# AMS_MCU.net
KiCad netlist of a schematic drawn in Altium Designer
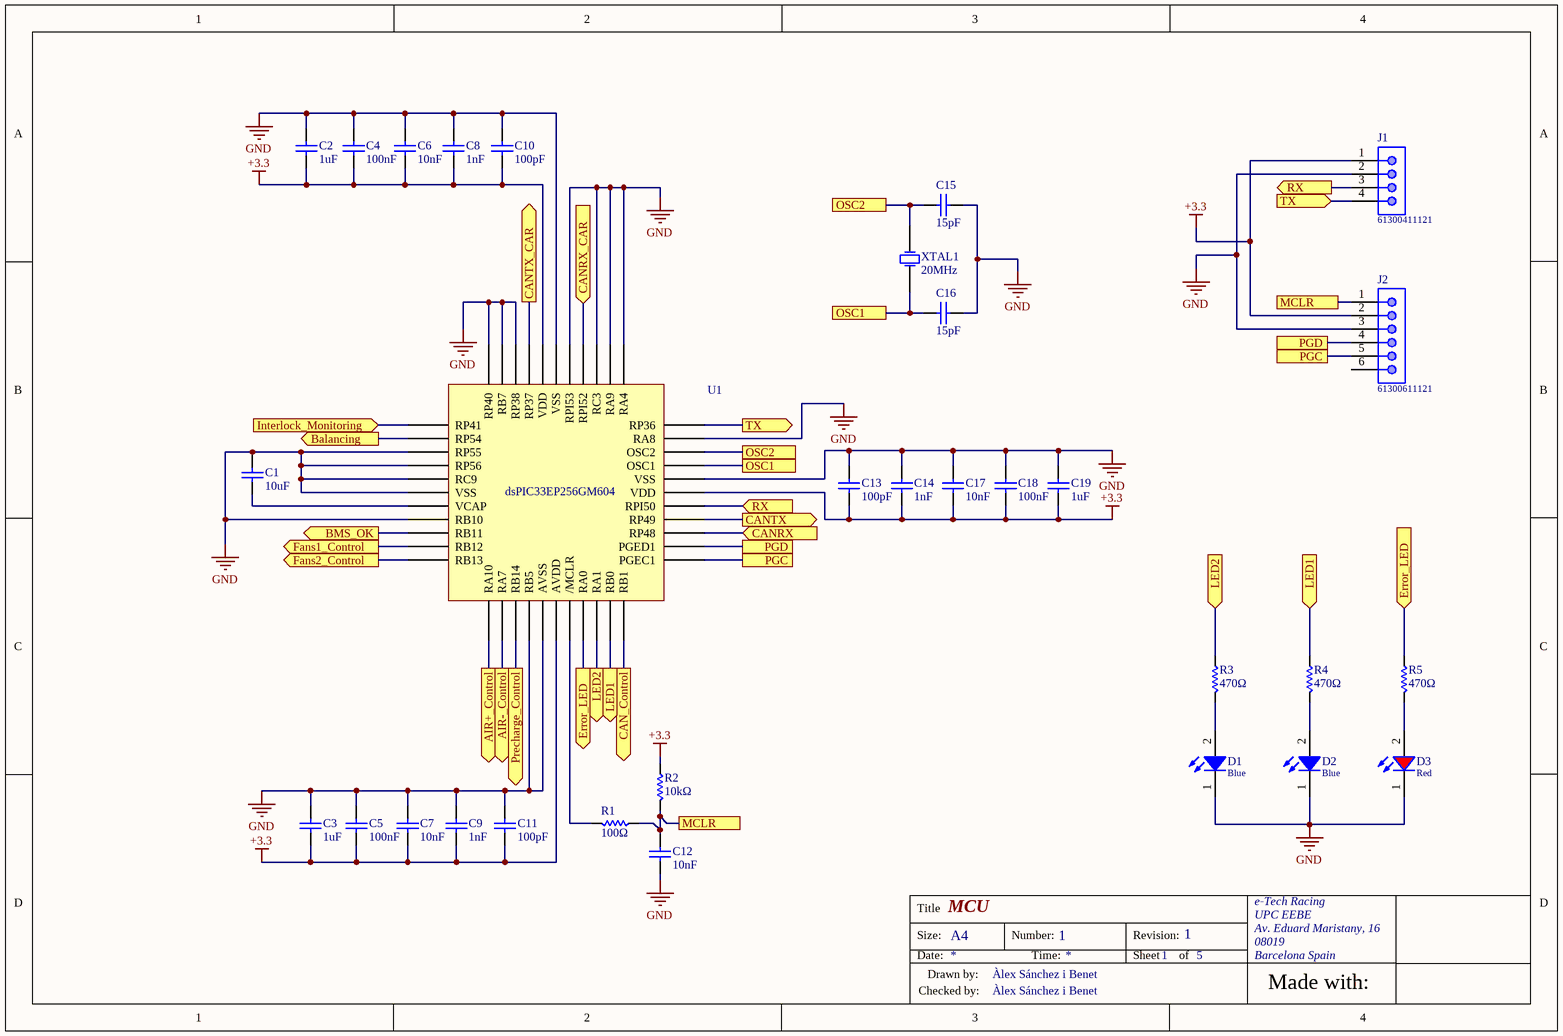
[diagram p0: AMS_MCU.SchDoc]

(export (version "E")
  (design (tool "Eeschema 10.0.6"))
  (components
    (comp (ref "C1")
      (value "10uF")
      (footprint "0805_2x1.25x1.25mm_Reflow Soldering")
      (description "WCAP-CSGP Ceramic Capacitors, 0805, X5R, 16V, 10uF")
      (fields (field (name "PART NUMBER") "885012107014") (field (name "PUBLISHER") "Wurth Elektronik"))
      (libsource (lib "Components_Library") (part "885012107014"))
    )
    (comp (ref "C2")
      (value "1uF")
      (footprint "0805_2x1.25x1.25mm_Reflow Soldering")
      (description "WCAP-CSGP Ceramic Capacitors, 0805, X7R, 50V, 1uF")
      (fields (field (name "PART NUMBER") "885012207103") (field (name "PUBLISHER") "Wurth Elektronik"))
      (libsource (lib "Components_Library") (part "885012207103"))
    )
    (comp (ref "C3")
      (value "1uF")
      (footprint "0805_2x1.25x1.25mm_Reflow Soldering")
      (description "WCAP-CSGP Ceramic Capacitors, 0805, X7R, 50V, 1uF")
      (fields (field (name "PART NUMBER") "885012207103") (field (name "PUBLISHER") "Wurth Elektronik"))
      (libsource (lib "Components_Library") (part "885012207103"))
    )
    (comp (ref "C4")
      (value "100nF")
      (footprint "0805_2x1.25x0.8mm_Reflow Soldering")
      (description "WCAP-CSGP Ceramic Capacitors, 0805, X7R, 50V, 100nF")
      (fields (field (name "PART NUMBER") "885012207098") (field (name "PUBLISHER") "Wurth Elektronik"))
      (libsource (lib "Components_Library") (part "885012207098"))
    )
    (comp (ref "C5")
      (value "100nF")
      (footprint "0805_2x1.25x0.8mm_Reflow Soldering")
      (description "WCAP-CSGP Ceramic Capacitors, 0805, X7R, 50V, 100nF")
      (fields (field (name "PART NUMBER") "885012207098") (field (name "PUBLISHER") "Wurth Elektronik"))
      (libsource (lib "Components_Library") (part "885012207098"))
    )
    (comp (ref "C6")
      (value "10nF")
      (footprint "0805_2x1.25x0.8mm_Reflow Soldering")
      (description "WCAP-CSGP Ceramic Capacitors, 0805, X7R, 50V, 10nF")
      (fields (field (name "PART NUMBER") "885012207092") (field (name "PUBLISHER") "Wurth Elektronik"))
      (libsource (lib "Components_Library") (part "885012207092"))
    )
    (comp (ref "C7")
      (value "10nF")
      (footprint "0805_2x1.25x0.8mm_Reflow Soldering")
      (description "WCAP-CSGP Ceramic Capacitors, 0805, X7R, 50V, 10nF")
      (fields (field (name "PART NUMBER") "885012207092") (field (name "PUBLISHER") "Wurth Elektronik"))
      (libsource (lib "Components_Library") (part "885012207092"))
    )
    (comp (ref "C8")
      (value "1nF")
      (footprint "0805_2x1.25x0.8mm_Reflow Soldering")
      (description "WCAP-CSGP Ceramic Capacitors, 0805, NP0, 50V, 1nF")
      (fields (field (name "PART NUMBER") "885012007063") (field (name "PUBLISHER") "Wurth Elektronik"))
      (libsource (lib "Components_Library") (part "885012007063"))
    )
    (comp (ref "C9")
      (value "1nF")
      (footprint "0805_2x1.25x0.8mm_Reflow Soldering")
      (description "WCAP-CSGP Ceramic Capacitors, 0805, NP0, 50V, 1nF")
      (fields (field (name "PART NUMBER") "885012007063") (field (name "PUBLISHER") "Wurth Elektronik"))
      (libsource (lib "Components_Library") (part "885012007063"))
    )
    (comp (ref "C10")
      (value "100pF")
      (footprint "0805_2x1.25x0.6mm_Reflow Soldering")
      (description "WCAP-CSGP Ceramic Capacitors, 0805, NP0, 50V, 100pF")
      (fields (field (name "PART NUMBER") "885012007057") (field (name "PUBLISHER") "Wurth Elektronik"))
      (libsource (lib "Components_Library") (part "885012007057"))
    )
    (comp (ref "C11")
      (value "100pF")
      (footprint "0805_2x1.25x0.6mm_Reflow Soldering")
      (description "WCAP-CSGP Ceramic Capacitors, 0805, NP0, 50V, 100pF")
      (fields (field (name "PART NUMBER") "885012007057") (field (name "PUBLISHER") "Wurth Elektronik"))
      (libsource (lib "Components_Library") (part "885012007057"))
    )
    (comp (ref "C12")
      (value "10nF")
      (footprint "0805_2x1.25x0.8mm_Reflow Soldering")
      (description "WCAP-CSGP Ceramic Capacitors, 0805, X7R, 50V, 10nF")
      (fields (field (name "PART NUMBER") "885012207092") (field (name "PUBLISHER") "Wurth Elektronik"))
      (libsource (lib "Components_Library") (part "885012207092"))
    )
    (comp (ref "C13")
      (value "100pF")
      (footprint "0805_2x1.25x0.6mm_Reflow Soldering")
      (description "WCAP-CSGP Ceramic Capacitors, 0805, NP0, 50V, 100pF")
      (fields (field (name "PART NUMBER") "885012007057") (field (name "PUBLISHER") "Wurth Elektronik"))
      (libsource (lib "Components_Library") (part "885012007057"))
    )
    (comp (ref "C14")
      (value "1nF")
      (footprint "0805_2x1.25x0.8mm_Reflow Soldering")
      (description "WCAP-CSGP Ceramic Capacitors, 0805, NP0, 50V, 1nF")
      (fields (field (name "PART NUMBER") "885012007063") (field (name "PUBLISHER") "Wurth Elektronik"))
      (libsource (lib "Components_Library") (part "885012007063"))
    )
    (comp (ref "C15")
      (value "15pF")
      (footprint "0805_2x1.25x0.6mm_Reflow Soldering")
      (description "WCAP-CSGP Ceramic Capacitors, 0805, NP0, 50V, 15pF")
      (fields (field (name "PART NUMBER") "885012007052") (field (name "PUBLISHER") "Wurth Elektronik"))
      (libsource (lib "Components_Library") (part "885012007052"))
    )
    (comp (ref "C16")
      (value "15pF")
      (footprint "0805_2x1.25x0.6mm_Reflow Soldering")
      (description "WCAP-CSGP Ceramic Capacitors, 0805, NP0, 50V, 15pF")
      (fields (field (name "PART NUMBER") "885012007052") (field (name "PUBLISHER") "Wurth Elektronik"))
      (libsource (lib "Components_Library") (part "885012007052"))
    )
    (comp (ref "C17")
      (value "10nF")
      (footprint "0805_2x1.25x0.8mm_Reflow Soldering")
      (description "WCAP-CSGP Ceramic Capacitors, 0805, X7R, 50V, 10nF")
      (fields (field (name "PART NUMBER") "885012207092") (field (name "PUBLISHER") "Wurth Elektronik"))
      (libsource (lib "Components_Library") (part "885012207092"))
    )
    (comp (ref "C18")
      (value "100nF")
      (footprint "0805_2x1.25x0.8mm_Reflow Soldering")
      (description "WCAP-CSGP Ceramic Capacitors, 0805, X7R, 50V, 100nF")
      (fields (field (name "PART NUMBER") "885012207098") (field (name "PUBLISHER") "Wurth Elektronik"))
      (libsource (lib "Components_Library") (part "885012207098"))
    )
    (comp (ref "C19")
      (value "1uF")
      (footprint "0805_2x1.25x1.25mm_Reflow Soldering")
      (description "WCAP-CSGP Ceramic Capacitors, 0805, X7R, 50V, 1uF")
      (fields (field (name "PART NUMBER") "885012207103") (field (name "PUBLISHER") "Wurth Elektronik"))
      (libsource (lib "Components_Library") (part "885012207103"))
    )
    (comp (ref "D1")
      (value "Blue")
      (footprint "WL-SMCW_0805")
      (description "SMT Mono-color Chip LED Waterclear WL-SMCW, size 0805, Blue, 3.2 V, 140 deg, 145 mcd")
      (fields (field (name "PART NUMBER") "150080BS75000") (field (name "PUBLISHER") "Wurth Elektronik"))
      (libsource (lib "Components_Library") (part "150080BS75000"))
    )
    (comp (ref "D2")
      (value "Blue")
      (footprint "WL-SMCW_0805")
      (description "SMT Mono-color Chip LED Waterclear WL-SMCW, size 0805, Blue, 3.2 V, 140 deg, 145 mcd")
      (fields (field (name "PART NUMBER") "150080BS75000") (field (name "PUBLISHER") "Wurth Elektronik"))
      (libsource (lib "Components_Library") (part "150080BS75000"))
    )
    (comp (ref "D3")
      (value "Red")
      (footprint "WL-SMCW_0805")
      (description "SMT Mono-color Chip LED Waterclear WL-SMCW, size 0805, Red, 2 V, 140 deg, 150 mcd")
      (fields (field (name "PART NUMBER") "150080RS75000") (field (name "PUBLISHER") "Wurth Elektronik"))
      (libsource (lib "Components_Library") (part "150080RS75000"))
    )
    (comp (ref "J1")
      (value "61300411121")
      (footprint "61300411121")
      (description "THT Vertical Pin Header WR-PHD, Pitch 2.54 mm, Single Row, 4 pins")
      (fields (field (name "PUBLISHER") "Wurth Elektronik"))
      (libsource (lib "Components_Library") (part "61300411121"))
    )
    (comp (ref "J2")
      (value "61300611121")
      (footprint "61300611121")
      (description "THT Vertical Pin Header WR-PHD, Pitch 2.54 mm, Single Row, 6 pins")
      (fields (field (name "PUBLISHER") "Wurth Elektronik"))
      (libsource (lib "Components_Library") (part "61300611121"))
    )
    (comp (ref "R1")
      (value "100Ω")
      (footprint "CR0805")
      (description "Chip Resistor 0805")
      (fields (field (name "MANUFACTURER") "Bourns"))
      (libsource (lib "Components_Library") (part "CR0805-FX-1000ELF"))
    )
    (comp (ref "R2")
      (value "10kΩ")
      (footprint "CR0805")
      (description "Chip Resistor 0805")
      (fields (field (name "MANUFACTURER") "Bourns"))
      (libsource (lib "Components_Library") (part "CR0805-JW-103ELF"))
    )
    (comp (ref "R3")
      (value "470Ω")
      (footprint "CR0805")
      (description "Chip Resistor 0805")
      (fields (field (name "MANUFACTURER") "Bourns"))
      (libsource (lib "Components_Library") (part "CR0805-FX-4700GLF"))
    )
    (comp (ref "R4")
      (value "470Ω")
      (footprint "CR0805")
      (description "Chip Resistor 0805")
      (fields (field (name "MANUFACTURER") "Bourns"))
      (libsource (lib "Components_Library") (part "CR0805-FX-4700GLF"))
    )
    (comp (ref "R5")
      (value "470Ω")
      (footprint "CR0805")
      (description "Chip Resistor 0805")
      (fields (field (name "MANUFACTURER") "Bourns"))
      (libsource (lib "Components_Library") (part "CR0805-FX-4700GLF"))
    )
    (comp (ref "U1")
      (value "dsPIC33EP256GM604")
      (footprint "dsPIC33EP256GM604")
      (description "16-Bit Digital Signal Controller with High-Speed PWM, Op Amps and Advanced Analog Features")
      (fields (field (name "MANUFACTURER") "Microchip"))
      (libsource (lib "Components_Library") (part "dsPIC33EP256GM604"))
    )
    (comp (ref "XTAL1")
      (value "20MHz")
      (footprint "830028710")
      (description "Industry standard SMD crystal WE-XTAL Quartz Crystal")
      (fields (field (name "MANUFACTURER") "Wurth Elektronik"))
      (libsource (lib "Components_Library") (part "830028710"))
    )
  )
  (nets
    (net (code "1") (name "+3.3") (class "Default")
      (node (ref "C10") (pin "1") (pinfunction "1_1") (pintype "passive"))
      (node (ref "C11") (pin "1") (pinfunction "1_1") (pintype "passive"))
      (node (ref "C13") (pin "1") (pinfunction "1_1") (pintype "passive"))
      (node (ref "C14") (pin "1") (pinfunction "1_1") (pintype "passive"))
      (node (ref "C17") (pin "1") (pinfunction "1_1") (pintype "passive"))
      (node (ref "C18") (pin "1") (pinfunction "1_1") (pintype "passive"))
      (node (ref "C19") (pin "1") (pinfunction "1_1") (pintype "passive"))
      (node (ref "C2") (pin "1") (pinfunction "1_1") (pintype "passive"))
      (node (ref "C3") (pin "1") (pinfunction "1_1") (pintype "passive"))
      (node (ref "C4") (pin "1") (pinfunction "1_1") (pintype "passive"))
      (node (ref "C5") (pin "1") (pinfunction "1_1") (pintype "passive"))
      (node (ref "C6") (pin "1") (pinfunction "1_1") (pintype "passive"))
      (node (ref "C7") (pin "1") (pinfunction "1_1") (pintype "passive"))
      (node (ref "C8") (pin "1") (pinfunction "1_1") (pintype "passive"))
      (node (ref "C9") (pin "1") (pinfunction "1_1") (pintype "passive"))
      (node (ref "J1") (pin "1") (pinfunction "1_1") (pintype "passive"))
      (node (ref "J2") (pin "2") (pinfunction "2_2") (pintype "passive"))
      (node (ref "R2") (pin "2") (pinfunction "2_2") (pintype "passive"))
      (node (ref "U1") (pin "17") (pinfunction "AVDD_17") (pintype "passive"))
      (node (ref "U1") (pin "28") (pinfunction "VDD_28") (pintype "passive"))
      (node (ref "U1") (pin "40") (pinfunction "VDD_40") (pintype "passive"))
    )
    (net (code "2") (name "/AIR+_Control") (class "Default")
      (node (ref "U1") (pin "12") (pinfunction "RA10_12") (pintype "passive"))
    )
    (net (code "3") (name "/AIR-_Control") (class "Default")
      (node (ref "U1") (pin "13") (pinfunction "RA7_13") (pintype "passive"))
    )
    (net (code "4") (name "/BMS_OK") (class "Default")
      (node (ref "U1") (pin "9") (pinfunction "RB11_9") (pintype "passive"))
    )
    (net (code "5") (name "/Balancing") (class "Default")
      (node (ref "U1") (pin "2") (pinfunction "RP54_2") (pintype "passive"))
    )
    (net (code "6") (name "/CANRX") (class "Default")
      (node (ref "U1") (pin "25") (pinfunction "RP48_25") (pintype "passive"))
    )
    (net (code "7") (name "/CANRX_CAR") (class "Default")
      (node (ref "U1") (pin "37") (pinfunction "RPI52_37") (pintype "passive"))
    )
    (net (code "8") (name "/CANTX") (class "Default")
      (node (ref "U1") (pin "26") (pinfunction "RP49_26") (pintype "passive"))
    )
    (net (code "9") (name "/CANTX_CAR") (class "Default")
      (node (ref "U1") (pin "41") (pinfunction "RP37_41") (pintype "passive"))
    )
    (net (code "10") (name "/CAN_Control") (class "Default")
      (node (ref "U1") (pin "22") (pinfunction "RB1_22") (pintype "passive"))
    )
    (net (code "11") (name "/Error_LED") (class "Default")
      (node (ref "R5") (pin "2") (pinfunction "2_2") (pintype "passive"))
      (node (ref "U1") (pin "19") (pinfunction "RA0_19") (pintype "passive"))
    )
    (net (code "12") (name "/Fans1_Control") (class "Default")
      (node (ref "U1") (pin "10") (pinfunction "RB12_10") (pintype "passive"))
    )
    (net (code "13") (name "/Fans2_Control") (class "Default")
      (node (ref "U1") (pin "11") (pinfunction "RB13_11") (pintype "passive"))
    )
    (net (code "14") (name "/Interlock_Monitoring") (class "Default")
      (node (ref "U1") (pin "1") (pinfunction "RP41_1") (pintype "passive"))
    )
    (net (code "15") (name "/LED1") (class "Default")
      (node (ref "R4") (pin "2") (pinfunction "2_2") (pintype "passive"))
      (node (ref "U1") (pin "21") (pinfunction "RB0_21") (pintype "passive"))
    )
    (net (code "16") (name "/LED2") (class "Default")
      (node (ref "R3") (pin "2") (pinfunction "2_2") (pintype "passive"))
      (node (ref "U1") (pin "20") (pinfunction "RA1_20") (pintype "passive"))
    )
    (net (code "17") (name "/MCLR") (class "Default")
      (node (ref "C12") (pin "2") (pinfunction "2_2") (pintype "passive"))
      (node (ref "J2") (pin "1") (pinfunction "1_1") (pintype "passive"))
      (node (ref "R1") (pin "2") (pinfunction "2_2") (pintype "passive"))
      (node (ref "R2") (pin "1") (pinfunction "1_1") (pintype "passive"))
    )
    (net (code "18") (name "/OSC1") (class "Default")
      (node (ref "C16") (pin "1") (pinfunction "1_1") (pintype "passive"))
      (node (ref "U1") (pin "30") (pinfunction "OSC1_30") (pintype "passive"))
      (node (ref "XTAL1") (pin "1") (pinfunction "OSC1_1") (pintype "passive"))
    )
    (net (code "19") (name "/OSC2") (class "Default")
      (node (ref "C15") (pin "1") (pinfunction "1_1") (pintype "passive"))
      (node (ref "U1") (pin "31") (pinfunction "OSC2_31") (pintype "passive"))
      (node (ref "XTAL1") (pin "2") (pinfunction "OSC2_2") (pintype "passive"))
    )
    (net (code "20") (name "/PGC") (class "Default")
      (node (ref "J2") (pin "5") (pinfunction "5_5") (pintype "passive"))
      (node (ref "U1") (pin "23") (pinfunction "PGEC1_23") (pintype "passive"))
    )
    (net (code "21") (name "/PGD") (class "Default")
      (node (ref "J2") (pin "4") (pinfunction "4_4") (pintype "passive"))
      (node (ref "U1") (pin "24") (pinfunction "PGED1_24") (pintype "passive"))
    )
    (net (code "22") (name "/Precharge_Control") (class "Default")
      (node (ref "U1") (pin "14") (pinfunction "RB14_14") (pintype "passive"))
    )
    (net (code "23") (name "/RX") (class "Default")
      (node (ref "J1") (pin "3") (pinfunction "3_3") (pintype "passive"))
      (node (ref "U1") (pin "27") (pinfunction "RPI50_27") (pintype "passive"))
    )
    (net (code "24") (name "/TX") (class "Default")
      (node (ref "J1") (pin "4") (pinfunction "4_4") (pintype "passive"))
      (node (ref "U1") (pin "33") (pinfunction "RP36_33") (pintype "passive"))
    )
    (net (code "25") (name "GND") (class "Default")
      (node (ref "C1") (pin "2") (pinfunction "2_2") (pintype "passive"))
      (node (ref "C10") (pin "2") (pinfunction "2_2") (pintype "passive"))
      (node (ref "C11") (pin "2") (pinfunction "2_2") (pintype "passive"))
      (node (ref "C12") (pin "1") (pinfunction "1_1") (pintype "passive"))
      (node (ref "C13") (pin "2") (pinfunction "2_2") (pintype "passive"))
      (node (ref "C14") (pin "2") (pinfunction "2_2") (pintype "passive"))
      (node (ref "C15") (pin "2") (pinfunction "2_2") (pintype "passive"))
      (node (ref "C16") (pin "2") (pinfunction "2_2") (pintype "passive"))
      (node (ref "C17") (pin "2") (pinfunction "2_2") (pintype "passive"))
      (node (ref "C18") (pin "2") (pinfunction "2_2") (pintype "passive"))
      (node (ref "C19") (pin "2") (pinfunction "2_2") (pintype "passive"))
      (node (ref "C2") (pin "2") (pinfunction "2_2") (pintype "passive"))
      (node (ref "C3") (pin "2") (pinfunction "2_2") (pintype "passive"))
      (node (ref "C4") (pin "2") (pinfunction "2_2") (pintype "passive"))
      (node (ref "C5") (pin "2") (pinfunction "2_2") (pintype "passive"))
      (node (ref "C6") (pin "2") (pinfunction "2_2") (pintype "passive"))
      (node (ref "C7") (pin "2") (pinfunction "2_2") (pintype "passive"))
      (node (ref "C8") (pin "2") (pinfunction "2_2") (pintype "passive"))
      (node (ref "C9") (pin "2") (pinfunction "2_2") (pintype "passive"))
      (node (ref "D1") (pin "1") (pinfunction "K_1") (pintype "passive"))
      (node (ref "D2") (pin "1") (pinfunction "K_1") (pintype "passive"))
      (node (ref "D3") (pin "1") (pinfunction "K_1") (pintype "passive"))
      (node (ref "J1") (pin "2") (pinfunction "2_2") (pintype "passive"))
      (node (ref "J2") (pin "3") (pinfunction "3_3") (pintype "passive"))
      (node (ref "U1") (pin "15") (pinfunction "RB5_15") (pintype "passive"))
      (node (ref "U1") (pin "16") (pinfunction "AVSS_16") (pintype "passive"))
      (node (ref "U1") (pin "29") (pinfunction "VSS_29") (pintype "passive"))
      (node (ref "U1") (pin "3") (pinfunction "RP55_3") (pintype "passive"))
      (node (ref "U1") (pin "32") (pinfunction "RA8_32") (pintype "passive"))
      (node (ref "U1") (pin "34") (pinfunction "RA4_34") (pintype "passive"))
      (node (ref "U1") (pin "35") (pinfunction "RA9_35") (pintype "passive"))
      (node (ref "U1") (pin "36") (pinfunction "RC3_36") (pintype "passive"))
      (node (ref "U1") (pin "38") (pinfunction "RPI53_38") (pintype "passive"))
      (node (ref "U1") (pin "39") (pinfunction "VSS_39") (pintype "passive"))
      (node (ref "U1") (pin "4") (pinfunction "RP56_4") (pintype "passive"))
      (node (ref "U1") (pin "42") (pinfunction "RP38_42") (pintype "passive"))
      (node (ref "U1") (pin "43") (pinfunction "RB7_43") (pintype "passive"))
      (node (ref "U1") (pin "44") (pinfunction "RP40_44") (pintype "passive"))
      (node (ref "U1") (pin "5") (pinfunction "RC9_5") (pintype "passive"))
      (node (ref "U1") (pin "6") (pinfunction "VSS_6") (pintype "passive"))
      (node (ref "U1") (pin "8") (pinfunction "RB10_8") (pintype "passive"))
    )
    (net (code "26") (name "Net-(D1-A)") (class "Default")
      (node (ref "D1") (pin "2") (pinfunction "A_2") (pintype "passive"))
      (node (ref "R3") (pin "1") (pinfunction "1_1") (pintype "passive"))
    )
    (net (code "27") (name "Net-(D2-A)") (class "Default")
      (node (ref "D2") (pin "2") (pinfunction "A_2") (pintype "passive"))
      (node (ref "R4") (pin "1") (pinfunction "1_1") (pintype "passive"))
    )
    (net (code "28") (name "Net-(D3-A)") (class "Default")
      (node (ref "D3") (pin "2") (pinfunction "A_2") (pintype "passive"))
      (node (ref "R5") (pin "1") (pinfunction "1_1") (pintype "passive"))
    )
    (net (code "29") (name "Net-(U1-VCAP)") (class "Default")
      (node (ref "C1") (pin "1") (pinfunction "1_1") (pintype "passive"))
      (node (ref "U1") (pin "7") (pinfunction "VCAP_7") (pintype "passive"))
    )
    (net (code "30") (name "Net-(U1-{slash}MCLR)") (class "Default")
      (node (ref "R1") (pin "1") (pinfunction "1_1") (pintype "passive"))
      (node (ref "U1") (pin "18") (pinfunction "/MCLR_18") (pintype "passive"))
    )
    (net (code "31") (name "unconnected-(J2-Pad6)") (class "Default")
      (node (ref "J2") (pin "6") (pinfunction "6_6") (pintype "passive"))
    )
  )
)
